# VCADual_Test.net
KiCad netlist of a schematic drawn in EAGLE
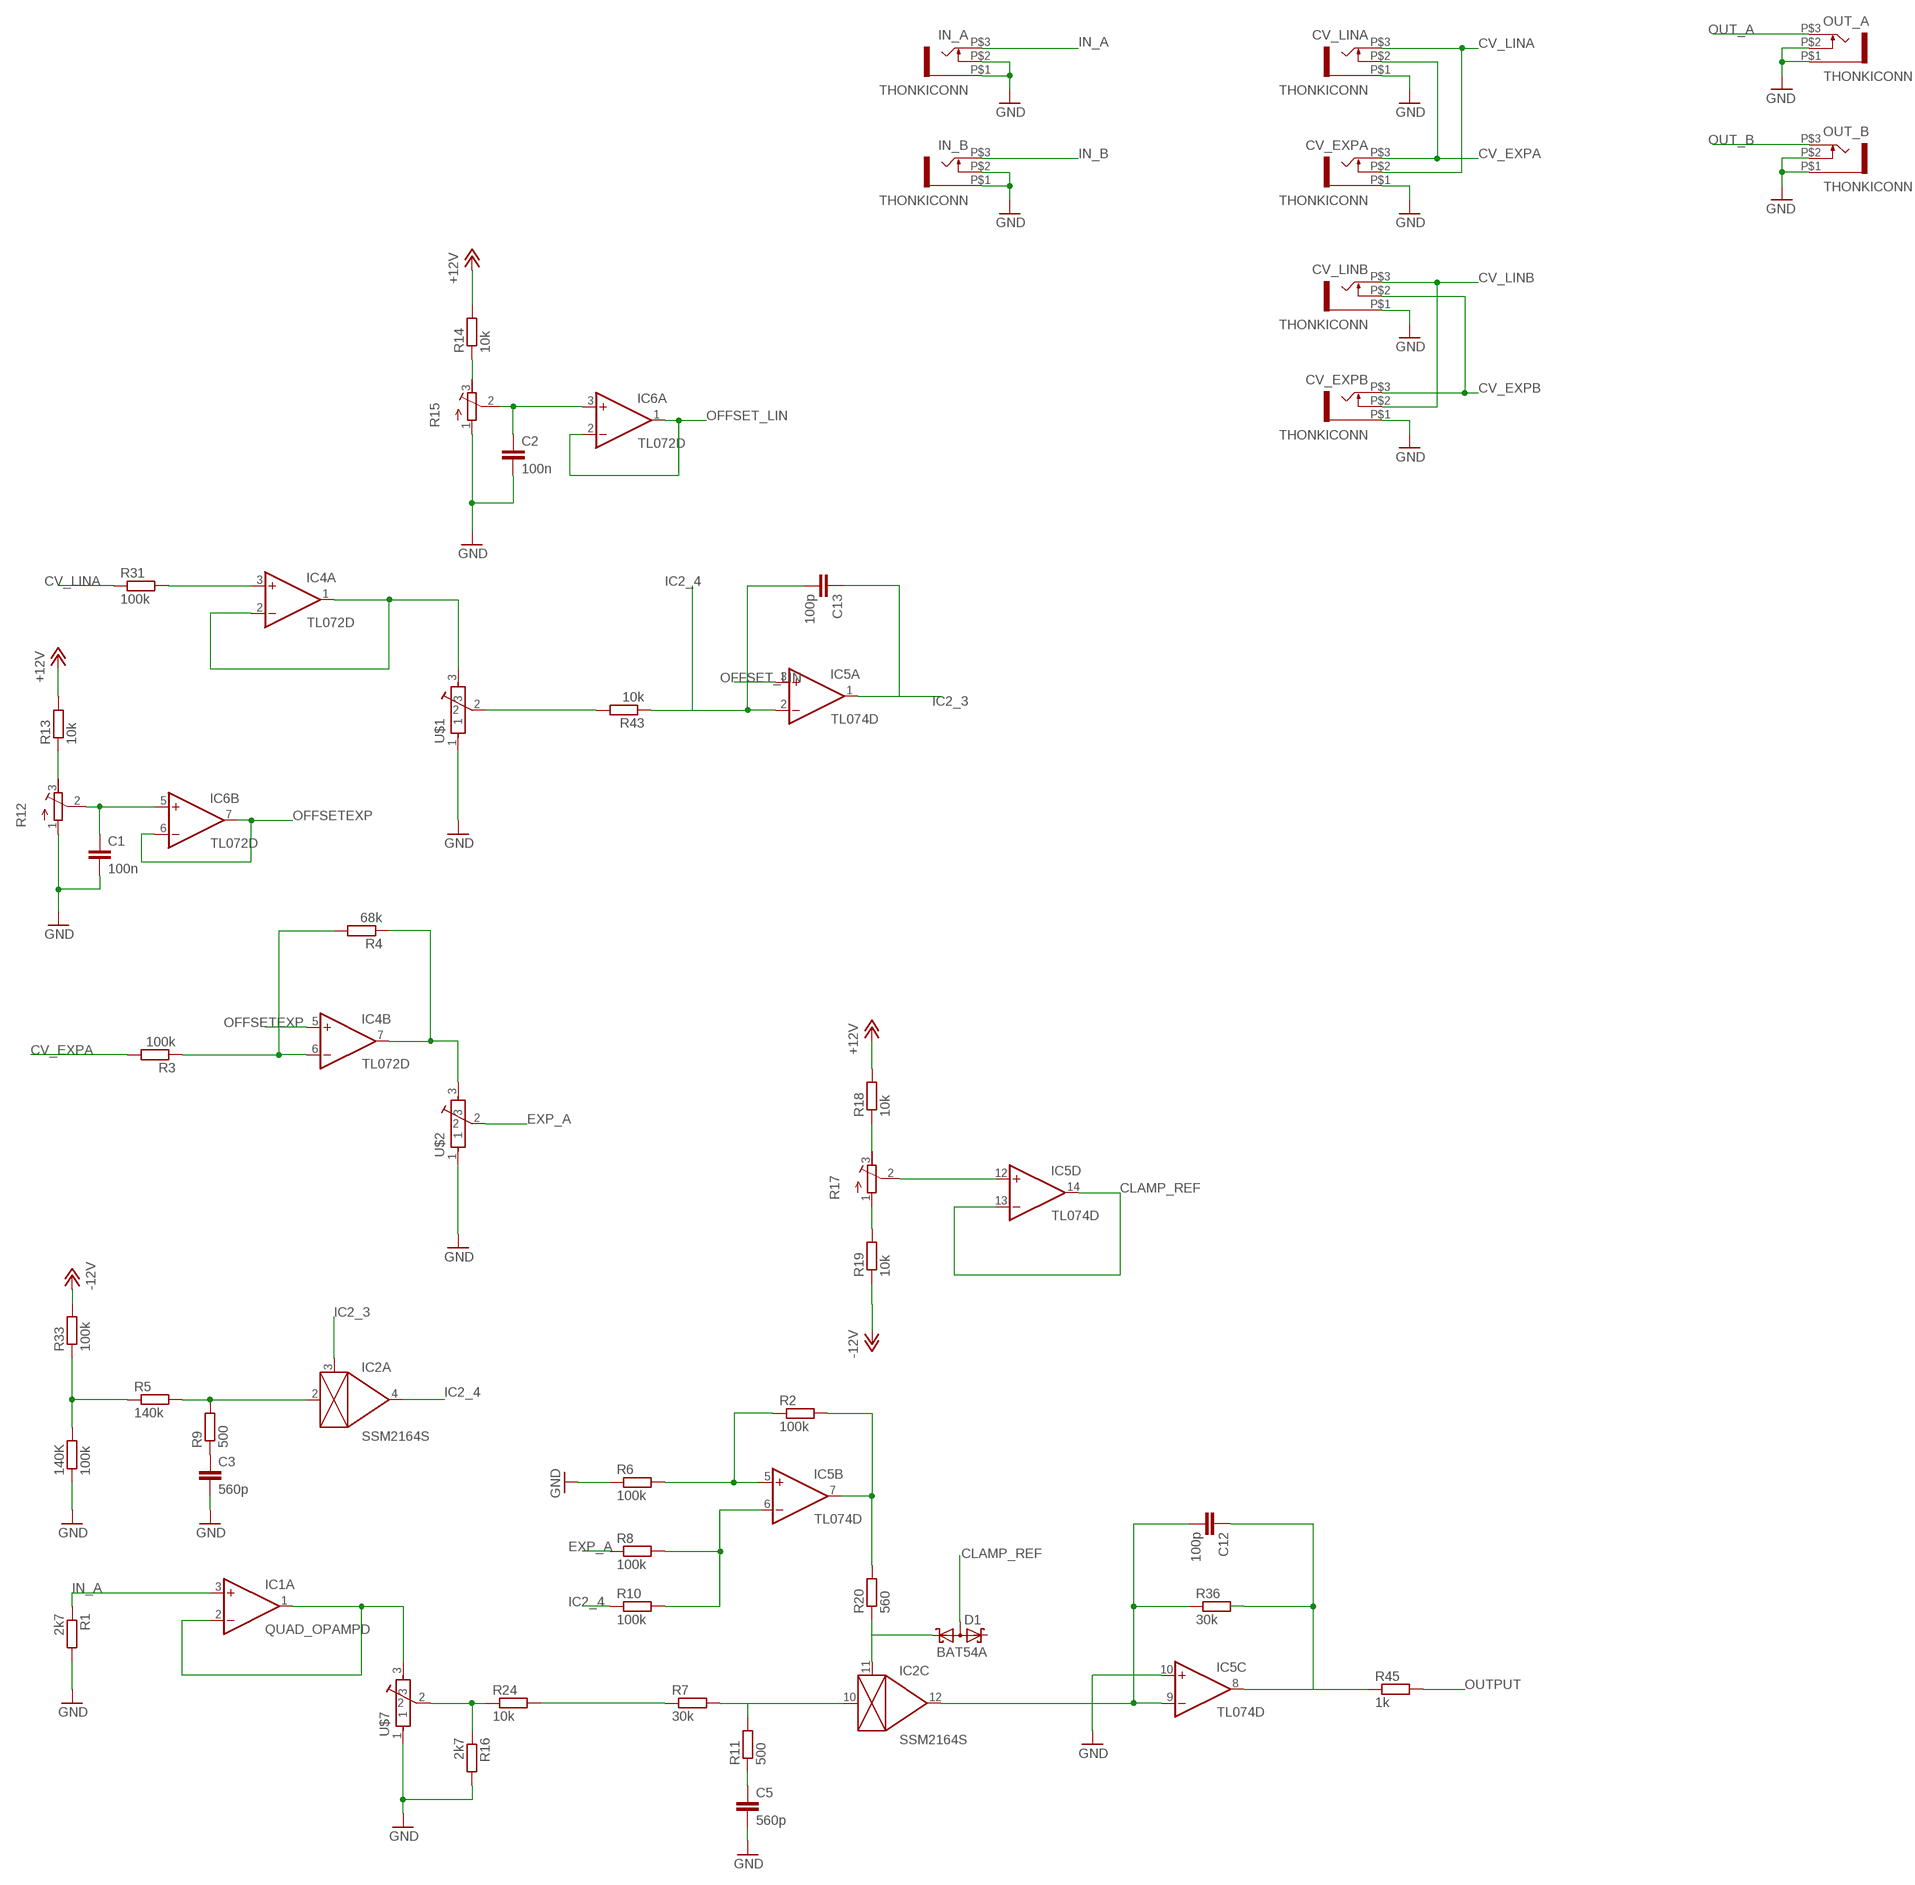
[diagram p0: schematic, sheet 1]

(export (version "E")
  (design (tool "Eeschema 10.0.6"))
  (components
    (comp (ref "140K")
      (value "100k")
      (footprint "eagle-import:0603")
      (libsource (lib "eagle-import") (part "R-EU_0603"))
    )
    (comp (ref "C1")
      (value "100n")
      (footprint "eagle-import:C0603K")
      (libsource (lib "eagle-import") (part "C-EUC0603K"))
    )
    (comp (ref "C2")
      (value "100n")
      (footprint "eagle-import:C0603K")
      (libsource (lib "eagle-import") (part "C-EUC0603K"))
    )
    (comp (ref "C3")
      (value "560p")
      (footprint "eagle-import:C0603K")
      (libsource (lib "eagle-import") (part "C-EUC0603K"))
    )
    (comp (ref "C5")
      (value "560p")
      (footprint "eagle-import:C0603K")
      (libsource (lib "eagle-import") (part "C-EUC0603K"))
    )
    (comp (ref "C12")
      (value "100p")
      (footprint "eagle-import:C0603K")
      (libsource (lib "eagle-import") (part "C-EUC0603K"))
    )
    (comp (ref "C13")
      (value "100p")
      (footprint "eagle-import:C0603K")
      (libsource (lib "eagle-import") (part "C-EUC0603K"))
    )
    (comp (ref "CV_EXPA")
      (value "THONKICONN")
      (footprint "eagle-import:THONKICONN")
      (libsource (lib "eagle-import") (part "THONKICONN"))
    )
    (comp (ref "CV_EXPB")
      (value "THONKICONN")
      (footprint "eagle-import:THONKICONN")
      (libsource (lib "eagle-import") (part "THONKICONN"))
    )
    (comp (ref "CV_LINA")
      (value "THONKICONN")
      (footprint "eagle-import:THONKICONN")
      (libsource (lib "eagle-import") (part "THONKICONN"))
    )
    (comp (ref "CV_LINB")
      (value "THONKICONN")
      (footprint "eagle-import:THONKICONN")
      (libsource (lib "eagle-import") (part "THONKICONN"))
    )
    (comp (ref "D1")
      (value "BAT54A")
      (footprint "eagle-import:SOT23")
      (libsource (lib "eagle-import") (part "BAT54A"))
    )
    (comp (ref "IC1")
      (value "QUAD_OPAMPD")
      (footprint "eagle-import:SO14")
      (libsource (lib "eagle-import") (part "QUAD_OPAMPD"))
    )
    (comp (ref "IC2")
      (value "SSM2164S")
      (footprint "eagle-import:SOIC16N")
      (libsource (lib "eagle-import") (part "SSM2164S"))
    )
    (comp (ref "IC4")
      (value "TL072D")
      (footprint "eagle-import:SO08")
      (libsource (lib "eagle-import") (part "TL072D"))
    )
    (comp (ref "IC5")
      (value "TL074D")
      (footprint "eagle-import:SO14")
      (libsource (lib "eagle-import") (part "TL074D"))
    )
    (comp (ref "IC6")
      (value "TL072D")
      (footprint "eagle-import:SO08")
      (libsource (lib "eagle-import") (part "TL072D"))
    )
    (comp (ref "IN_A")
      (value "THONKICONN")
      (footprint "eagle-import:THONKICONN")
      (libsource (lib "eagle-import") (part "THONKICONN"))
    )
    (comp (ref "IN_B")
      (value "THONKICONN")
      (footprint "eagle-import:THONKICONN")
      (libsource (lib "eagle-import") (part "THONKICONN"))
    )
    (comp (ref "OUT_A")
      (value "THONKICONN")
      (footprint "eagle-import:THONKICONN")
      (libsource (lib "eagle-import") (part "THONKICONN"))
    )
    (comp (ref "OUT_B")
      (value "THONKICONN")
      (footprint "eagle-import:THONKICONN")
      (libsource (lib "eagle-import") (part "THONKICONN"))
    )
    (comp (ref "R1")
      (value "2k7")
      (footprint "eagle-import:0603")
      (libsource (lib "eagle-import") (part "R-EU_0603"))
    )
    (comp (ref "R2")
      (value "100k")
      (footprint "eagle-import:0603")
      (libsource (lib "eagle-import") (part "R-EU_0603"))
    )
    (comp (ref "R3")
      (value "100k")
      (footprint "eagle-import:0603")
      (libsource (lib "eagle-import") (part "R-EU_0603"))
    )
    (comp (ref "R4")
      (value "68k")
      (footprint "eagle-import:0603")
      (libsource (lib "eagle-import") (part "R-EU_0603"))
    )
    (comp (ref "R5")
      (value "140k")
      (footprint "eagle-import:0603")
      (libsource (lib "eagle-import") (part "R-EU_0603"))
    )
    (comp (ref "R6")
      (value "100k")
      (footprint "eagle-import:0603")
      (libsource (lib "eagle-import") (part "R-EU_0603"))
    )
    (comp (ref "R7")
      (value "30k")
      (footprint "eagle-import:0603")
      (libsource (lib "eagle-import") (part "R-EU_0603"))
    )
    (comp (ref "R8")
      (value "100k")
      (footprint "eagle-import:0603")
      (libsource (lib "eagle-import") (part "R-EU_0603"))
    )
    (comp (ref "R9")
      (value "500")
      (footprint "eagle-import:0603")
      (libsource (lib "eagle-import") (part "R-EU_0603"))
    )
    (comp (ref "R10")
      (value "100k")
      (footprint "eagle-import:0603")
      (libsource (lib "eagle-import") (part "R-EU_0603"))
    )
    (comp (ref "R11")
      (value "500")
      (footprint "eagle-import:0603")
      (libsource (lib "eagle-import") (part "R-EU_0603"))
    )
    (comp (ref "R12")
      (value "R-TRIMM64X")
      (footprint "eagle-import:RTRIM64X")
      (libsource (lib "eagle-import") (part "R-TRIMM64X"))
    )
    (comp (ref "R13")
      (value "10k")
      (footprint "eagle-import:0603")
      (libsource (lib "eagle-import") (part "R-EU_0603"))
    )
    (comp (ref "R14")
      (value "10k")
      (footprint "eagle-import:0603")
      (libsource (lib "eagle-import") (part "R-EU_0603"))
    )
    (comp (ref "R15")
      (value "R-TRIMM64X")
      (footprint "eagle-import:RTRIM64X")
      (libsource (lib "eagle-import") (part "R-TRIMM64X"))
    )
    (comp (ref "R16")
      (value "2k7")
      (footprint "eagle-import:0603")
      (libsource (lib "eagle-import") (part "R-EU_0603"))
    )
    (comp (ref "R17")
      (value "R-TRIMM64X")
      (footprint "eagle-import:RTRIM64X")
      (libsource (lib "eagle-import") (part "R-TRIMM64X"))
    )
    (comp (ref "R18")
      (value "10k")
      (footprint "eagle-import:0603")
      (libsource (lib "eagle-import") (part "R-EU_0603"))
    )
    (comp (ref "R19")
      (value "10k")
      (footprint "eagle-import:0603")
      (libsource (lib "eagle-import") (part "R-EU_0603"))
    )
    (comp (ref "R20")
      (value "560")
      (footprint "eagle-import:0603")
      (libsource (lib "eagle-import") (part "R-EU_0603"))
    )
    (comp (ref "R24")
      (value "10k")
      (footprint "eagle-import:0603")
      (libsource (lib "eagle-import") (part "R-EU_0603"))
    )
    (comp (ref "R31")
      (value "100k")
      (footprint "eagle-import:0603")
      (libsource (lib "eagle-import") (part "R-EU_0603"))
    )
    (comp (ref "R33")
      (value "100k")
      (footprint "eagle-import:0603")
      (libsource (lib "eagle-import") (part "R-EU_0603"))
    )
    (comp (ref "R36")
      (value "30k")
      (footprint "eagle-import:0603")
      (libsource (lib "eagle-import") (part "R-EU_0603"))
    )
    (comp (ref "R43")
      (value "10k")
      (footprint "eagle-import:0603")
      (libsource (lib "eagle-import") (part "R-EU_0603"))
    )
    (comp (ref "R45")
      (value "1k")
      (footprint "eagle-import:0603")
      (libsource (lib "eagle-import") (part "R-EU_0603"))
    )
    (comp (ref "U$1")
      (value "POT-ALPS-RK09L1140")
      (footprint "eagle-import:POT-ALPS-RK09L1140")
      (libsource (lib "eagle-import") (part "POT-ALPS-RK09L1140"))
    )
    (comp (ref "U$2")
      (value "POT-ALPS-RK09L1140")
      (footprint "eagle-import:POT-ALPS-RK09L1140")
      (libsource (lib "eagle-import") (part "POT-ALPS-RK09L1140"))
    )
    (comp (ref "U$7")
      (value "POT-ALPS-RK09L1140")
      (footprint "eagle-import:POT-ALPS-RK09L1140")
      (libsource (lib "eagle-import") (part "POT-ALPS-RK09L1140"))
    )
  )
  (nets
    (net (code "1") (name "+12V") (class "Default")
      (node (ref "R13") (pin "2") (pinfunction "2_2") (pintype "passive"))
      (node (ref "R14") (pin "2") (pinfunction "2_2") (pintype "passive"))
      (node (ref "R18") (pin "2") (pinfunction "2_2") (pintype "passive"))
    )
    (net (code "2") (name "-12V") (class "Default")
      (node (ref "R19") (pin "1") (pinfunction "1_1") (pintype "passive"))
      (node (ref "R33") (pin "2") (pinfunction "2_2") (pintype "passive"))
    )
    (net (code "3") (name "/CLAMP_REF") (class "Default")
      (node (ref "D1") (pin "1") (pinfunction "K1_1") (pintype "passive"))
      (node (ref "D1") (pin "3") (pinfunction "AA_3") (pintype "passive"))
      (node (ref "IC2") (pin "11") (pinfunction "CTRL_11") (pintype "input"))
      (node (ref "IC5") (pin "13") (pinfunction "-IN_13") (pintype "input"))
      (node (ref "IC5") (pin "14") (pinfunction "OUT_14") (pintype "output"))
      (node (ref "R20") (pin "1") (pinfunction "1_1") (pintype "passive"))
    )
    (net (code "4") (name "/CV_EXPA") (class "Default")
      (node (ref "CV_EXPA") (pin "P$3") (pinfunction "3_P$3") (pintype "passive"))
      (node (ref "CV_LINA") (pin "P$2") (pinfunction "4_P$2") (pintype "passive"))
      (node (ref "R3") (pin "2") (pinfunction "2_2") (pintype "passive"))
    )
    (net (code "5") (name "/CV_EXPB") (class "Default")
      (node (ref "CV_EXPB") (pin "P$3") (pinfunction "3_P$3") (pintype "passive"))
      (node (ref "CV_LINB") (pin "P$2") (pinfunction "4_P$2") (pintype "passive"))
    )
    (net (code "6") (name "/CV_LINA") (class "Default")
      (node (ref "CV_EXPA") (pin "P$2") (pinfunction "4_P$2") (pintype "passive"))
      (node (ref "CV_LINA") (pin "P$3") (pinfunction "3_P$3") (pintype "passive"))
      (node (ref "R31") (pin "1") (pinfunction "1_1") (pintype "passive"))
    )
    (net (code "7") (name "/CV_LINB") (class "Default")
      (node (ref "CV_EXPB") (pin "P$2") (pinfunction "4_P$2") (pintype "passive"))
      (node (ref "CV_LINB") (pin "P$3") (pinfunction "3_P$3") (pintype "passive"))
    )
    (net (code "8") (name "/EXP_A") (class "Default")
      (node (ref "R8") (pin "1") (pinfunction "1_1") (pintype "passive"))
      (node (ref "U$2") (pin "2") (pinfunction "2_2") (pintype "bidirectional"))
    )
    (net (code "9") (name "/IC2_3") (class "Default")
      (node (ref "C13") (pin "1") (pinfunction "1_1") (pintype "passive"))
      (node (ref "IC2") (pin "3") (pinfunction "CTRL_3") (pintype "input"))
      (node (ref "IC5") (pin "1") (pinfunction "OUT_1") (pintype "output"))
    )
    (net (code "10") (name "/IC2_4") (class "Default")
      (node (ref "C13") (pin "2") (pinfunction "2_2") (pintype "passive"))
      (node (ref "IC2") (pin "4") (pinfunction "OUT_4") (pintype "output"))
      (node (ref "IC5") (pin "2") (pinfunction "-IN_2") (pintype "input"))
      (node (ref "R10") (pin "1") (pinfunction "1_1") (pintype "passive"))
      (node (ref "R43") (pin "1") (pinfunction "1_1") (pintype "passive"))
    )
    (net (code "11") (name "/IN_A") (class "Default")
      (node (ref "IC1") (pin "3") (pinfunction "+IN_3") (pintype "input"))
      (node (ref "IN_A") (pin "P$3") (pinfunction "3_P$3") (pintype "passive"))
      (node (ref "R1") (pin "1") (pinfunction "1_1") (pintype "passive"))
    )
    (net (code "12") (name "/IN_B") (class "Default")
      (node (ref "IN_B") (pin "P$3") (pinfunction "3_P$3") (pintype "passive"))
    )
    (net (code "13") (name "/OFFSETEXP") (class "Default")
      (node (ref "IC4") (pin "5") (pinfunction "+IN_5") (pintype "input"))
      (node (ref "IC6") (pin "6") (pinfunction "-IN_6") (pintype "input"))
      (node (ref "IC6") (pin "7") (pinfunction "OUT_7") (pintype "output"))
    )
    (net (code "14") (name "/OFFSET_LIN") (class "Default")
      (node (ref "IC5") (pin "3") (pinfunction "+IN_3") (pintype "input"))
      (node (ref "IC6") (pin "1") (pinfunction "OUT_1") (pintype "output"))
      (node (ref "IC6") (pin "2") (pinfunction "-IN_2") (pintype "input"))
    )
    (net (code "15") (name "/OUTPUT") (class "Default")
      (node (ref "R45") (pin "2") (pinfunction "2_2") (pintype "passive"))
    )
    (net (code "16") (name "/OUT_A") (class "Default")
      (node (ref "OUT_A") (pin "P$3") (pinfunction "3_P$3") (pintype "passive"))
    )
    (net (code "17") (name "/OUT_B") (class "Default")
      (node (ref "OUT_B") (pin "P$3") (pinfunction "3_P$3") (pintype "passive"))
    )
    (net (code "18") (name "GND") (class "Default")
      (node (ref "140K") (pin "1") (pinfunction "1_1") (pintype "passive"))
      (node (ref "C1") (pin "2") (pinfunction "2_2") (pintype "passive"))
      (node (ref "C2") (pin "2") (pinfunction "2_2") (pintype "passive"))
      (node (ref "C3") (pin "2") (pinfunction "2_2") (pintype "passive"))
      (node (ref "C5") (pin "2") (pinfunction "2_2") (pintype "passive"))
      (node (ref "CV_EXPA") (pin "P$1") (pinfunction "5_P$1") (pintype "passive"))
      (node (ref "CV_EXPB") (pin "P$1") (pinfunction "5_P$1") (pintype "passive"))
      (node (ref "CV_LINA") (pin "P$1") (pinfunction "5_P$1") (pintype "passive"))
      (node (ref "CV_LINB") (pin "P$1") (pinfunction "5_P$1") (pintype "passive"))
      (node (ref "IC5") (pin "10") (pinfunction "+IN_10") (pintype "input"))
      (node (ref "IN_A") (pin "P$1") (pinfunction "5_P$1") (pintype "passive"))
      (node (ref "IN_A") (pin "P$2") (pinfunction "4_P$2") (pintype "passive"))
      (node (ref "IN_B") (pin "P$1") (pinfunction "5_P$1") (pintype "passive"))
      (node (ref "IN_B") (pin "P$2") (pinfunction "4_P$2") (pintype "passive"))
      (node (ref "OUT_A") (pin "P$1") (pinfunction "5_P$1") (pintype "passive"))
      (node (ref "OUT_A") (pin "P$2") (pinfunction "4_P$2") (pintype "passive"))
      (node (ref "OUT_B") (pin "P$1") (pinfunction "5_P$1") (pintype "passive"))
      (node (ref "OUT_B") (pin "P$2") (pinfunction "4_P$2") (pintype "passive"))
      (node (ref "R1") (pin "2") (pinfunction "2_2") (pintype "passive"))
      (node (ref "R12") (pin "1") (pinfunction "A_1") (pintype "passive"))
      (node (ref "R15") (pin "1") (pinfunction "A_1") (pintype "passive"))
      (node (ref "R16") (pin "2") (pinfunction "2_2") (pintype "passive"))
      (node (ref "R6") (pin "1") (pinfunction "1_1") (pintype "passive"))
      (node (ref "U$1") (pin "1") (pinfunction "1_1") (pintype "bidirectional"))
      (node (ref "U$2") (pin "1") (pinfunction "1_1") (pintype "bidirectional"))
      (node (ref "U$7") (pin "1") (pinfunction "1_1") (pintype "bidirectional"))
    )
    (net (code "19") (name "Net-(140K-Pad2)") (class "Default")
      (node (ref "140K") (pin "2") (pinfunction "2_2") (pintype "passive"))
      (node (ref "R33") (pin "1") (pinfunction "1_1") (pintype "passive"))
      (node (ref "R5") (pin "1") (pinfunction "1_1") (pintype "passive"))
    )
    (net (code "20") (name "Net-(C3-Pad1)") (class "Default")
      (node (ref "C3") (pin "1") (pinfunction "1_1") (pintype "passive"))
      (node (ref "R9") (pin "1") (pinfunction "1_1") (pintype "passive"))
    )
    (net (code "21") (name "Net-(C5-Pad1)") (class "Default")
      (node (ref "C5") (pin "1") (pinfunction "1_1") (pintype "passive"))
      (node (ref "R11") (pin "1") (pinfunction "1_1") (pintype "passive"))
    )
    (net (code "22") (name "Net-(IC1A--IN)") (class "Default")
      (node (ref "IC1") (pin "1") (pinfunction "OUT_1") (pintype "output"))
      (node (ref "IC1") (pin "2") (pinfunction "-IN_2") (pintype "input"))
      (node (ref "U$7") (pin "3") (pinfunction "3_3") (pintype "bidirectional"))
    )
    (net (code "23") (name "Net-(IC2A-IN)") (class "Default")
      (node (ref "IC2") (pin "2") (pinfunction "IN_2") (pintype "input"))
      (node (ref "R5") (pin "2") (pinfunction "2_2") (pintype "passive"))
      (node (ref "R9") (pin "2") (pinfunction "2_2") (pintype "passive"))
    )
    (net (code "24") (name "Net-(IC2C-IN)") (class "Default")
      (node (ref "IC2") (pin "10") (pinfunction "IN_10") (pintype "input"))
      (node (ref "R11") (pin "2") (pinfunction "2_2") (pintype "passive"))
      (node (ref "R7") (pin "2") (pinfunction "2_2") (pintype "passive"))
    )
    (net (code "25") (name "Net-(IC2C-OUT)") (class "Default")
      (node (ref "C12") (pin "2") (pinfunction "2_2") (pintype "passive"))
      (node (ref "IC2") (pin "12") (pinfunction "OUT_12") (pintype "output"))
      (node (ref "IC5") (pin "9") (pinfunction "-IN_9") (pintype "input"))
      (node (ref "R36") (pin "1") (pinfunction "1_1") (pintype "passive"))
    )
    (net (code "26") (name "Net-(IC4A-+IN)") (class "Default")
      (node (ref "IC4") (pin "3") (pinfunction "+IN_3") (pintype "input"))
      (node (ref "R31") (pin "2") (pinfunction "2_2") (pintype "passive"))
    )
    (net (code "27") (name "Net-(IC4A--IN)") (class "Default")
      (node (ref "IC4") (pin "1") (pinfunction "OUT_1") (pintype "output"))
      (node (ref "IC4") (pin "2") (pinfunction "-IN_2") (pintype "input"))
      (node (ref "U$1") (pin "3") (pinfunction "3_3") (pintype "bidirectional"))
    )
    (net (code "28") (name "Net-(IC4B--IN)") (class "Default")
      (node (ref "IC4") (pin "6") (pinfunction "-IN_6") (pintype "input"))
      (node (ref "R3") (pin "1") (pinfunction "1_1") (pintype "passive"))
      (node (ref "R4") (pin "2") (pinfunction "2_2") (pintype "passive"))
    )
    (net (code "29") (name "Net-(IC4B-OUT)") (class "Default")
      (node (ref "IC4") (pin "7") (pinfunction "OUT_7") (pintype "output"))
      (node (ref "R4") (pin "1") (pinfunction "1_1") (pintype "passive"))
      (node (ref "U$2") (pin "3") (pinfunction "3_3") (pintype "bidirectional"))
    )
    (net (code "30") (name "Net-(IC5B-+IN)") (class "Default")
      (node (ref "IC5") (pin "5") (pinfunction "+IN_5") (pintype "input"))
      (node (ref "R2") (pin "1") (pinfunction "1_1") (pintype "passive"))
      (node (ref "R6") (pin "2") (pinfunction "2_2") (pintype "passive"))
    )
    (net (code "31") (name "Net-(IC5B-OUT)") (class "Default")
      (node (ref "IC5") (pin "7") (pinfunction "OUT_7") (pintype "output"))
      (node (ref "R2") (pin "2") (pinfunction "2_2") (pintype "passive"))
      (node (ref "R20") (pin "2") (pinfunction "2_2") (pintype "passive"))
    )
    (net (code "32") (name "Net-(IC5C-OUT)") (class "Default")
      (node (ref "C12") (pin "1") (pinfunction "1_1") (pintype "passive"))
      (node (ref "IC5") (pin "8") (pinfunction "OUT_8") (pintype "output"))
      (node (ref "R36") (pin "2") (pinfunction "2_2") (pintype "passive"))
      (node (ref "R45") (pin "1") (pinfunction "1_1") (pintype "passive"))
    )
    (net (code "33") (name "Net-(IC5D-+IN)") (class "Default")
      (node (ref "IC5") (pin "12") (pinfunction "+IN_12") (pintype "input"))
      (node (ref "R17") (pin "2") (pinfunction "S_2") (pintype "passive"))
    )
    (net (code "34") (name "Net-(IC6A-+IN)") (class "Default")
      (node (ref "C2") (pin "1") (pinfunction "1_1") (pintype "passive"))
      (node (ref "IC6") (pin "3") (pinfunction "+IN_3") (pintype "input"))
      (node (ref "R15") (pin "2") (pinfunction "S_2") (pintype "passive"))
    )
    (net (code "35") (name "Net-(IC6B-+IN)") (class "Default")
      (node (ref "C1") (pin "1") (pinfunction "1_1") (pintype "passive"))
      (node (ref "IC6") (pin "5") (pinfunction "+IN_5") (pintype "input"))
      (node (ref "R12") (pin "2") (pinfunction "S_2") (pintype "passive"))
    )
    (net (code "36") (name "Net-(R10-Pad2)") (class "Default")
      (node (ref "R10") (pin "2") (pinfunction "2_2") (pintype "passive"))
      (node (ref "R8") (pin "2") (pinfunction "2_2") (pintype "passive"))
    )
    (net (code "37") (name "Net-(R12-E)") (class "Default")
      (node (ref "R12") (pin "3") (pinfunction "E_3") (pintype "passive"))
      (node (ref "R13") (pin "1") (pinfunction "1_1") (pintype "passive"))
    )
    (net (code "38") (name "Net-(R15-E)") (class "Default")
      (node (ref "R14") (pin "1") (pinfunction "1_1") (pintype "passive"))
      (node (ref "R15") (pin "3") (pinfunction "E_3") (pintype "passive"))
    )
    (net (code "39") (name "Net-(R16-Pad1)") (class "Default")
      (node (ref "R16") (pin "1") (pinfunction "1_1") (pintype "passive"))
      (node (ref "R24") (pin "1") (pinfunction "1_1") (pintype "passive"))
      (node (ref "U$7") (pin "2") (pinfunction "2_2") (pintype "bidirectional"))
    )
    (net (code "40") (name "Net-(R17-A)") (class "Default")
      (node (ref "R17") (pin "1") (pinfunction "A_1") (pintype "passive"))
      (node (ref "R19") (pin "2") (pinfunction "2_2") (pintype "passive"))
    )
    (net (code "41") (name "Net-(R17-E)") (class "Default")
      (node (ref "R17") (pin "3") (pinfunction "E_3") (pintype "passive"))
      (node (ref "R18") (pin "1") (pinfunction "1_1") (pintype "passive"))
    )
    (net (code "42") (name "Net-(R24-Pad2)") (class "Default")
      (node (ref "R24") (pin "2") (pinfunction "2_2") (pintype "passive"))
      (node (ref "R7") (pin "1") (pinfunction "1_1") (pintype "passive"))
    )
    (net (code "43") (name "Net-(R43-Pad2)") (class "Default")
      (node (ref "R43") (pin "2") (pinfunction "2_2") (pintype "passive"))
      (node (ref "U$1") (pin "2") (pinfunction "2_2") (pintype "bidirectional"))
    )
    (net (code "44") (name "unconnected-(D1-K2-Pad2)") (class "Default")
      (node (ref "D1") (pin "2") (pinfunction "K2_2") (pintype "passive"))
    )
    (net (code "45") (name "unconnected-(IC5B--IN-Pad6)") (class "Default")
      (node (ref "IC5") (pin "6") (pinfunction "-IN_6") (pintype "input"))
    )
  )
)
